# 15_-_PWR_IN_LEDS_BUTTONS_MECH.net
KiCad netlist of a schematic drawn in Altium Designer
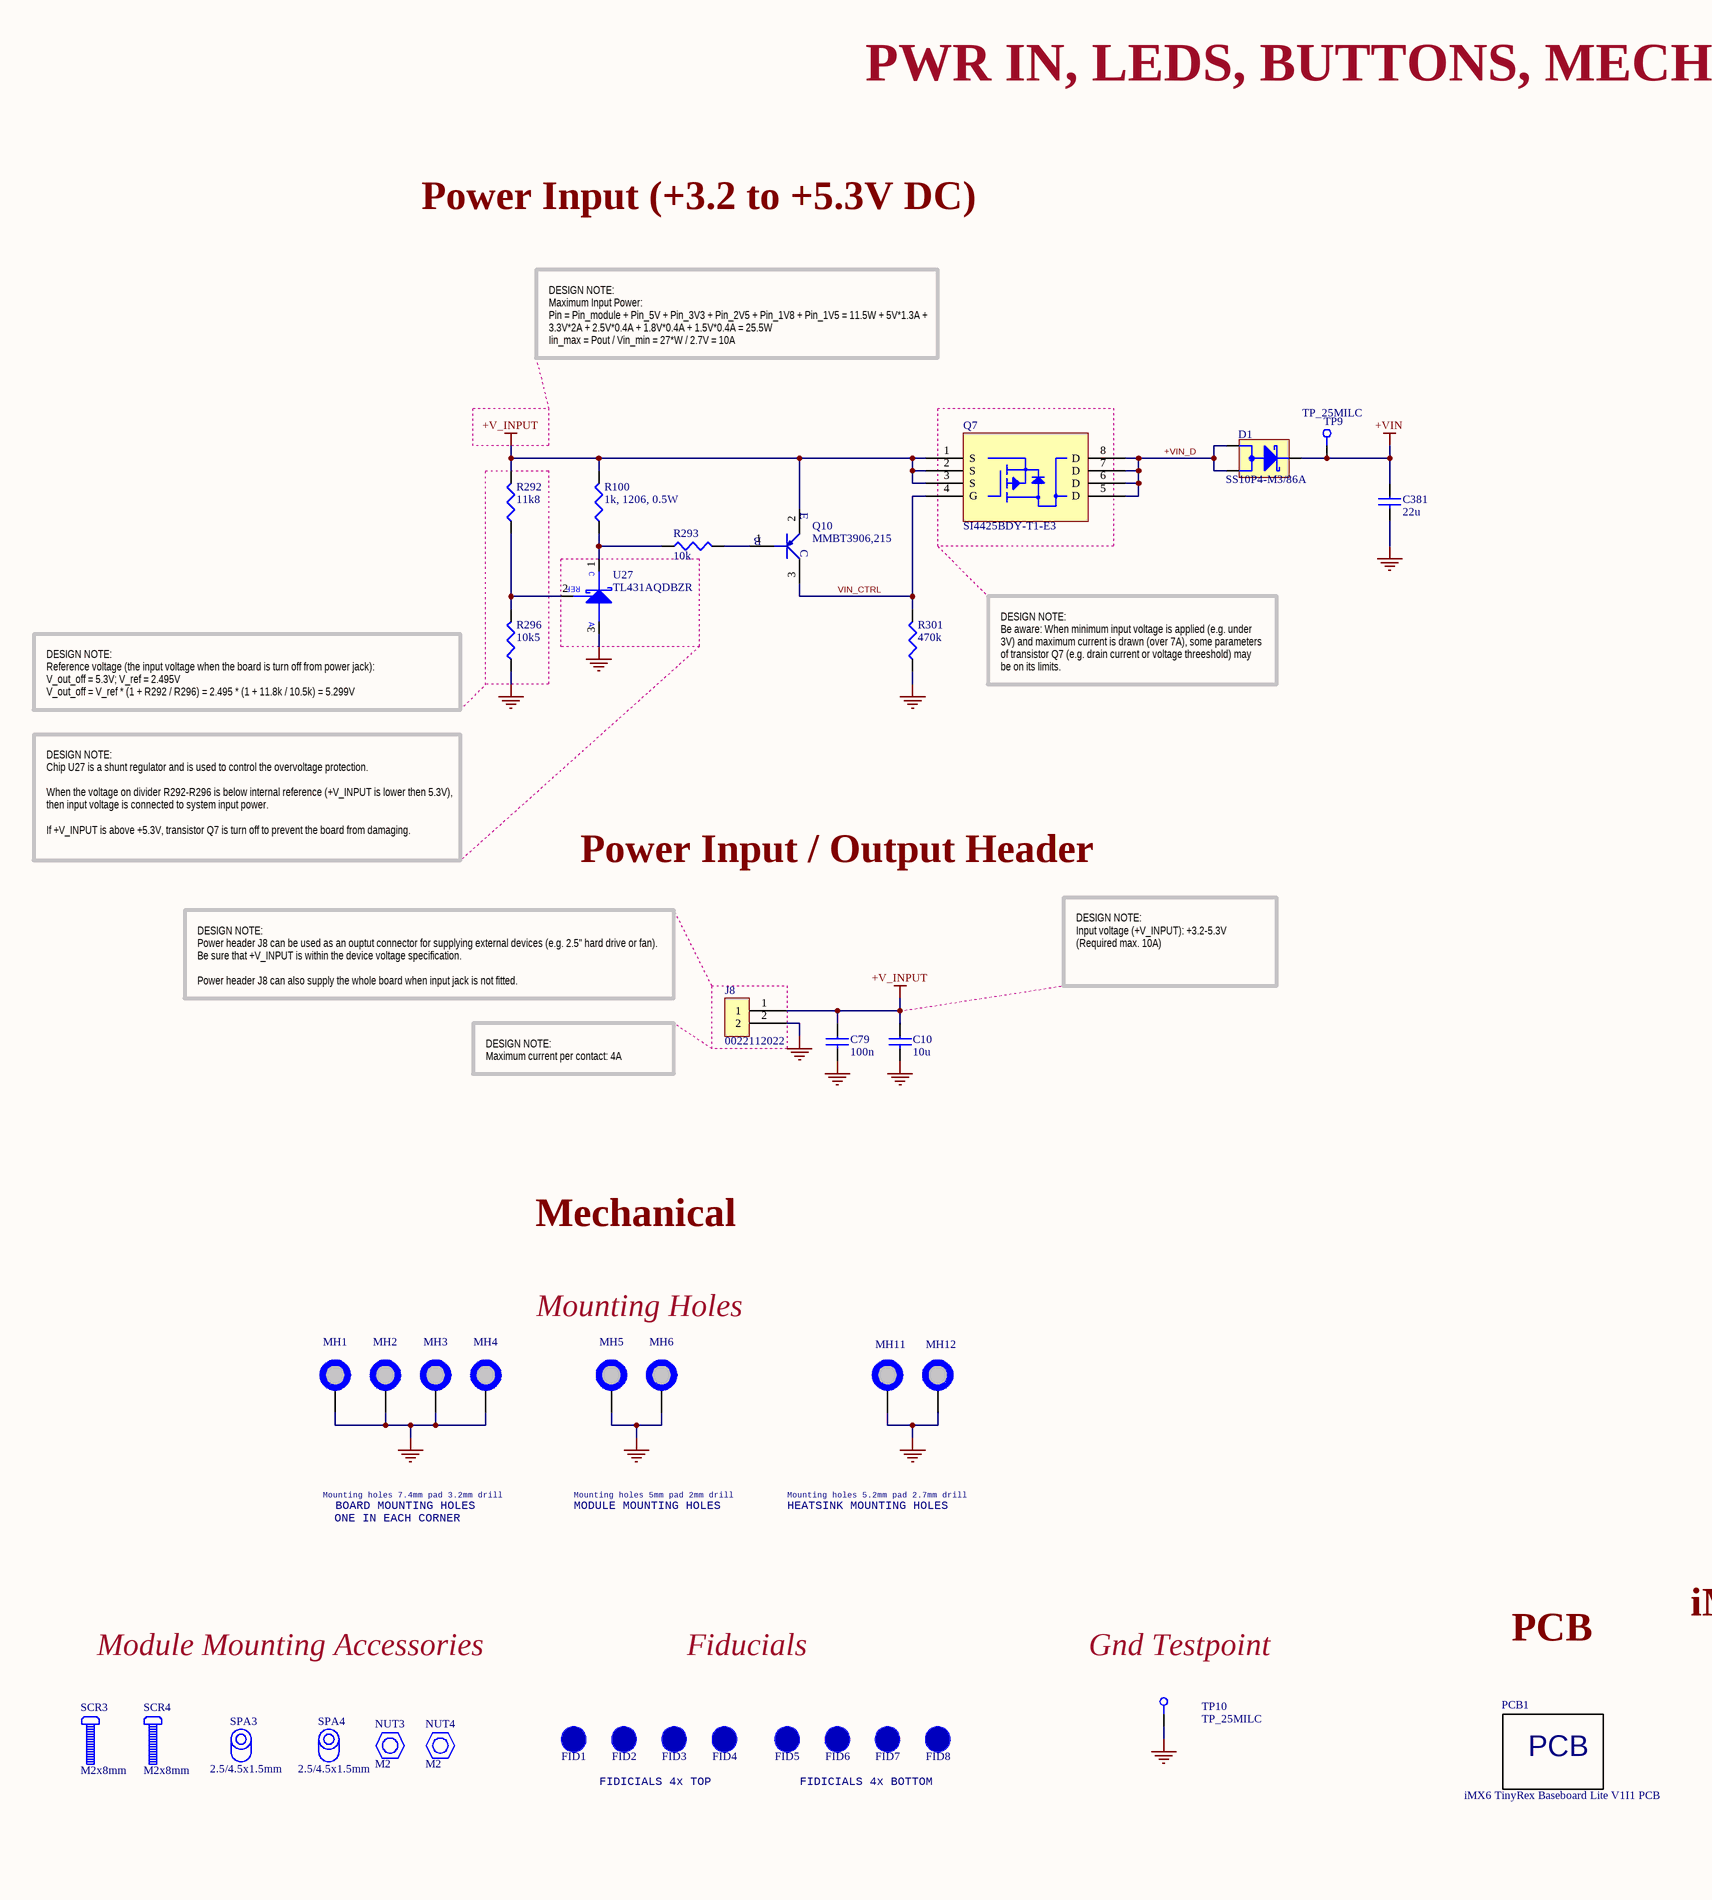
[diagram p0: [15] - PWR IN, LEDS, BUTTONS, MECH.SchDoc, left]
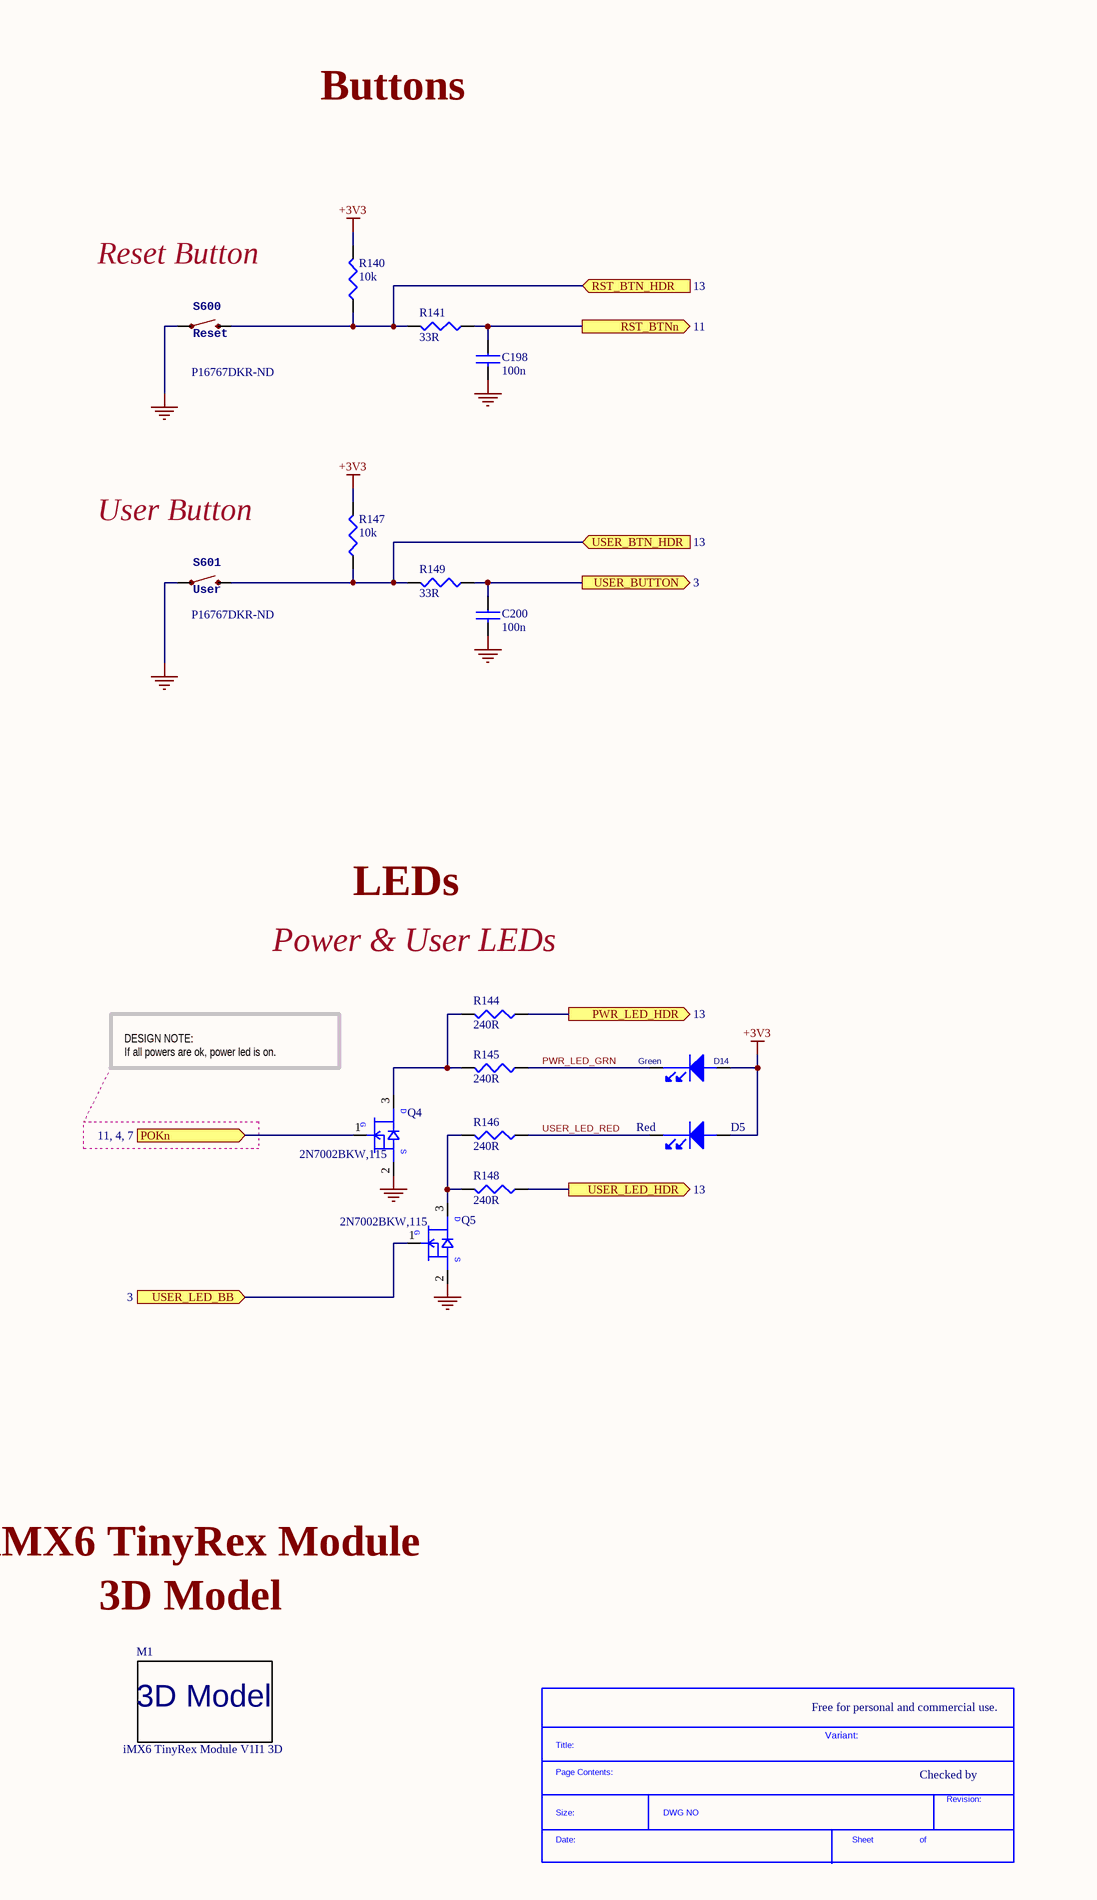
[diagram p1: [15] - PWR IN, LEDS, BUTTONS, MECH.SchDoc, right]

(export (version "E")
  (design (tool "Eeschema 10.0.6"))
  (components
    (comp (ref "C10")
      (value "10u")
      (footprint "C0603")
      (description "CAP CER 10UF 6.3V X5R 20% 0603")
      (fields
        (field (name "MANUFACTURER") "TDK Corporation")
        (field (name "MANUFACTURER PART NUMBER") "C1608X5R0J106M")
      )
      (libsource (lib "Integrated_Library_FEDEVEL_APR_2015") (part "C1608X5R0J106M"))
    )
    (comp (ref "C79")
      (value "100n")
      (footprint "C0402")
      (description "CAP CER .10UF 50V X5R 10% 0402")
      (fields
        (field (name "MANUFACTURER") "TDK Corporation")
        (field (name "MANUFACTURER PART NUMBER") "C1005X5R1H104K")
      )
      (libsource (lib "Integrated_Library_FEDEVEL_APR_2015") (part "C1005X5R1H104K"))
    )
    (comp (ref "C198")
      (value "100n")
      (footprint "C0402")
      (description "CAP CER .10UF 50V X5R 10% 0402")
      (fields
        (field (name "MANUFACTURER") "TDK Corporation")
        (field (name "MANUFACTURER PART NUMBER") "C1005X5R1H104K")
      )
      (libsource (lib "Integrated_Library_FEDEVEL_APR_2015") (part "C1005X5R1H104K"))
    )
    (comp (ref "C200")
      (value "100n")
      (footprint "C0402")
      (description "CAP CER .10UF 50V X5R 10% 0402")
      (fields
        (field (name "MANUFACTURER") "TDK Corporation")
        (field (name "MANUFACTURER PART NUMBER") "C1005X5R1H104K")
      )
      (libsource (lib "Integrated_Library_FEDEVEL_APR_2015") (part "C1005X5R1H104K"))
    )
    (comp (ref "C381")
      (value "22u")
      (footprint "C0603")
      (description "CAP CER 22UF 6.3V 20% X5R 0603")
      (fields
        (field (name "MANUFACTURER") "TDK Corporation")
        (field (name "MANUFACTURER PART NUMBER") "C1608X5R0J226M080AC")
        (field (name ".CREATOR") "MM")
        (field (name ".CHECKED PCB") "MM")
        (field (name ".CHECKED SCH") "MM")
      )
      (libsource (lib "Integrated_Library_FEDEVEL_APR_2015") (part "C1608X5R0J226M080AC"))
    )
    (comp (ref "D1")
      (value "SS10P4-M3/86A")
      (footprint "TO-277A (SMPC)")
      (description "DIODE SCHOTTKY 40V 10A TO277A")
      (fields
        (field (name "MANUFACTURER") "Vishay Semiconductor Diodes Division")
        (field (name ".CHECKED PCB") "MM")
        (field (name ".CHECKED SCH") "MM")
        (field (name ".CREATOR") "MM")
      )
      (libsource (lib "Integrated_Library_FEDEVEL_APR_2015") (part "SS10P4-M3/86A"))
    )
    (comp (ref "D5")
      (value "Red")
      (footprint "LED_0603")
      (description "LED SMARTLED RED 630NM 0603 SMD")
      (fields
        (field (name "MANUFACTURER") "OSRAM Opto Semiconductors Inc")
        (field (name "MANUFACTURER PART NUMBER") "LS L29K-H1J2-1-Z")
      )
      (libsource (lib "Integrated_Library_FEDEVEL_APR_2015") (part "LS L29K-H1J2-1-Z"))
    )
    (comp (ref "D14")
      (value "Green")
      (footprint "LED_0603")
      (description "LED SMARTLED GREEN 570NM 0603")
      (fields
        (field (name "MANUFACTURER") "OSRAM Opto Semiconductors Inc")
        (field (name "MANUFACTURER PART NUMBER") "LG L29K-G2J1-24-Z")
      )
      (libsource (lib "Integrated_Library_FEDEVEL_APR_2015") (part "LG L29K-G2J1-24-Z"))
    )
    (comp (ref "FID1")
      (value "FID_1MMC")
      (footprint "FID_40X120D")
      (description "Fiducial 40mil Diameter, 120mil Mask")
      (libsource (lib "Integrated_Library_FEDEVEL_APR_2015") (part "FID_1MMC"))
    )
    (comp (ref "FID2")
      (value "FID_1MMC")
      (footprint "FID_40X120D")
      (description "Fiducial 40mil Diameter, 120mil Mask")
      (libsource (lib "Integrated_Library_FEDEVEL_APR_2015") (part "FID_1MMC"))
    )
    (comp (ref "FID3")
      (value "FID_1MMC")
      (footprint "FID_40X120D")
      (description "Fiducial 40mil Diameter, 120mil Mask")
      (libsource (lib "Integrated_Library_FEDEVEL_APR_2015") (part "FID_1MMC"))
    )
    (comp (ref "FID4")
      (value "FID_1MMC")
      (footprint "FID_40X120D")
      (description "Fiducial 40mil Diameter, 120mil Mask")
      (libsource (lib "Integrated_Library_FEDEVEL_APR_2015") (part "FID_1MMC"))
    )
    (comp (ref "FID5")
      (value "FID_1MMC")
      (footprint "FID_40X120D")
      (description "Fiducial 40mil Diameter, 120mil Mask")
      (libsource (lib "Integrated_Library_FEDEVEL_APR_2015") (part "FID_1MMC"))
    )
    (comp (ref "FID6")
      (value "FID_1MMC")
      (footprint "FID_40X120D")
      (description "Fiducial 40mil Diameter, 120mil Mask")
      (libsource (lib "Integrated_Library_FEDEVEL_APR_2015") (part "FID_1MMC"))
    )
    (comp (ref "FID7")
      (value "FID_1MMC")
      (footprint "FID_40X120D")
      (description "Fiducial 40mil Diameter, 120mil Mask")
      (libsource (lib "Integrated_Library_FEDEVEL_APR_2015") (part "FID_1MMC"))
    )
    (comp (ref "FID8")
      (value "FID_1MMC")
      (footprint "FID_40X120D")
      (description "Fiducial 40mil Diameter, 120mil Mask")
      (libsource (lib "Integrated_Library_FEDEVEL_APR_2015") (part "FID_1MMC"))
    )
    (comp (ref "J8")
      (value "0022112022")
      (footprint "HDR_1x2_2.54MM_MOLEX_KK")
      (description "CONN HEADER 2POS .100 VERT GOLD")
      (fields
        (field (name "MANUFACTURER") "Molex, LLC")
        (field (name ".CREATOR") "MM")
        (field (name ".CHECKED SCH") "MM")
        (field (name ".CHECKED PCB") "MM, paper model not checked")
      )
      (libsource (lib "Integrated_Library_FEDEVEL_APR_2015") (part "0022112022"))
    )
    (comp (ref "M1")
      (value "iMX6 TinyRex Module V1I1 3D")
      (footprint "iMX6 TinyRex Module 3D")
      (description "3D Model")
      (fields (field (name ".CREATOR") "MM"))
      (libsource (lib "Integrated_Library_FEDEVEL_APR_2015") (part "3D_iMX6_TINYREX_MODULE_V1I1"))
    )
    (comp (ref "MH1")
      (value "MH_7.4MMC_3.2MMD")
      (footprint "MH_7.4MMD_3.2MMD")
      (description "Mounting Hole 7.4mm Diameter, 3.2mm Drill")
      (fields (field (name ".CREATOR") "MM"))
      (libsource (lib "Integrated_Library_FEDEVEL_APR_2015") (part "MH_7.4MMC_3.2MMD"))
    )
    (comp (ref "MH2")
      (value "MH_7.4MMC_3.2MMD")
      (footprint "MH_7.4MMD_3.2MMD")
      (description "Mounting Hole 7.4mm Diameter, 3.2mm Drill")
      (fields (field (name ".CREATOR") "MM"))
      (libsource (lib "Integrated_Library_FEDEVEL_APR_2015") (part "MH_7.4MMC_3.2MMD"))
    )
    (comp (ref "MH3")
      (value "MH_7.4MMC_3.2MMD")
      (footprint "MH_7.4MMD_3.2MMD")
      (description "Mounting Hole 7.4mm Diameter, 3.2mm Drill")
      (fields (field (name ".CREATOR") "MM"))
      (libsource (lib "Integrated_Library_FEDEVEL_APR_2015") (part "MH_7.4MMC_3.2MMD"))
    )
    (comp (ref "MH4")
      (value "MH_7.4MMC_3.2MMD")
      (footprint "MH_7.4MMD_3.2MMD")
      (description "Mounting Hole 7.4mm Diameter, 3.2mm Drill")
      (fields (field (name ".CREATOR") "MM"))
      (libsource (lib "Integrated_Library_FEDEVEL_APR_2015") (part "MH_7.4MMC_3.2MMD"))
    )
    (comp (ref "MH5")
      (value "MH_5MMC_2MMD")
      (footprint "MH_5MMD_2MMD")
      (description "Mounting Hole 5mm Diameter, 2mm Drill")
      (fields (field (name ".CREATOR") "MM"))
      (libsource (lib "Integrated_Library_FEDEVEL_APR_2015") (part "MH_5MMC_2MMD"))
    )
    (comp (ref "MH6")
      (value "MH_5MMC_2MMD")
      (footprint "MH_5MMD_2MMD")
      (description "Mounting Hole 5mm Diameter, 2mm Drill")
      (fields (field (name ".CREATOR") "MM"))
      (libsource (lib "Integrated_Library_FEDEVEL_APR_2015") (part "MH_5MMC_2MMD"))
    )
    (comp (ref "MH11")
      (value "MH_5.2MMC_2.7MMD")
      (footprint "MH_5.2MMD_2.7MMD")
      (description "Mounting Hole 5.2mm Diameter, 2.7mm Drill")
      (fields (field (name ".CREATOR") "MM"))
      (libsource (lib "Integrated_Library_FEDEVEL_APR_2015") (part "MH_5.2MMC_2.7MMD"))
    )
    (comp (ref "MH12")
      (value "MH_5.2MMC_2.7MMD")
      (footprint "MH_5.2MMD_2.7MMD")
      (description "Mounting Hole 5.2mm Diameter, 2.7mm Drill")
      (fields (field (name ".CREATOR") "MM"))
      (libsource (lib "Integrated_Library_FEDEVEL_APR_2015") (part "MH_5.2MMC_2.7MMD"))
    )
    (comp (ref "NUT3")
      (value "M2")
      (footprint "NUT A4 SS M2")
      (description "ROEBUCK - PFP1166 - FULL NUT A4 SS M2 (PK 100)")
      (fields
        (field (name "MANUFACTURER") "ROEBUCK")
        (field (name "MANUFACTURER PART NUMBER") "PFP1166")
        (field (name ".CHECKED SCH") "MM")
      )
      (libsource (lib "Integrated_Library_FEDEVEL_APR_2015") (part "PFP1166"))
    )
    (comp (ref "NUT4")
      (value "M2")
      (footprint "NUT A4 SS M2")
      (description "ROEBUCK - PFP1166 - FULL NUT A4 SS M2 (PK 100)")
      (fields
        (field (name "MANUFACTURER") "ROEBUCK")
        (field (name "MANUFACTURER PART NUMBER") "PFP1166")
        (field (name ".CHECKED SCH") "MM")
      )
      (libsource (lib "Integrated_Library_FEDEVEL_APR_2015") (part "PFP1166"))
    )
    (comp (ref "PCB1")
      (value "iMX6 TinyRex Baseboard Lite V1I1 PCB")
      (fields (field (name ".CREATOR") "MM") (field (name ".CHECKED SCH") "MM"))
      (libsource (lib "Integrated_Library_FEDEVEL_APR_2015") (part "PCB_iMX6_TinyRex_Baseboard_Lite_V1I1"))
    )
    (comp (ref "Q4")
      (value "2N7002BKW,115")
      (footprint "SC70_SOT323")
      (description "MOSFET N-CH 60V 310MA SOT323")
      (fields (field (name "MANUFACTURER") "NXP Semiconductors"))
      (libsource (lib "Integrated_Library_FEDEVEL_APR_2015") (part "2N7002BKW,115"))
    )
    (comp (ref "Q5")
      (value "2N7002BKW,115")
      (footprint "SC70_SOT323")
      (description "MOSFET N-CH 60V 310MA SOT323")
      (fields (field (name "MANUFACTURER") "NXP Semiconductors"))
      (libsource (lib "Integrated_Library_FEDEVEL_APR_2015") (part "2N7002BKW,115"))
    )
    (comp (ref "Q7")
      (value "SI4425BDY-T1-E3")
      (footprint "8_SOIC_3.9MM")
      (description "MOSFET P-CH 30V 8.8A 8-SOIC")
      (fields
        (field (name "MANUFACTURER") "Vishay Siliconix")
        (field (name ".CHECKED PCB") "MM")
        (field (name ".CHECKED SCH") "MM")
        (field (name ".CREATOR") "MM")
      )
      (libsource (lib "Integrated_Library_FEDEVEL_APR_2015") (part "SI4425BDY-T1-E3"))
    )
    (comp (ref "Q10")
      (value "MMBT3906,215")
      (footprint "SOT-23-3-123")
      (description "TRANS PNP 40V 0.2A SOT23")
      (fields
        (field (name "MANUFACTURER") "NXP Semiconductors")
        (field (name ".CHECKED PCB") "MM")
        (field (name ".CHECKED SCH") "MM")
        (field (name ".CREATOR") "MM")
      )
      (libsource (lib "Integrated_Library_FEDEVEL_APR_2015") (part "MMBT3906,215"))
    )
    (comp (ref "R100")
      (value "1k, 1206, 0.5W")
      (footprint "R1206")
      (description "RES SMD 1K OHM 1% 1/2W 1206")
      (fields
        (field (name "MANUFACTURER") "Stackpole Electronics Inc")
        (field (name "MANUFACTURER PART NUMBER") "RNCP1206FTD1K00")
        (field (name ".CHECKED PCB") "MM")
        (field (name ".CHECKED SCH") "MM")
        (field (name ".CREATOR") "MM")
      )
      (libsource (lib "Integrated_Library_FEDEVEL_APR_2015") (part "RNCP1206FTD1K00"))
    )
    (comp (ref "R140")
      (value "10k")
      (footprint "R0402")
      (description "RES 10.0K OHM 1/16W 1% 0402 SMD")
      (fields
        (field (name "MANUFACTURER") "Yageo")
        (field (name "MANUFACTURER PART NUMBER") "RC0402FR-0710KL")
      )
      (libsource (lib "Integrated_Library_FEDEVEL_APR_2015") (part "RC0402FR-0710KL"))
    )
    (comp (ref "R141")
      (value "33R")
      (footprint "R0402")
      (description "RES TF 33 OHM 1% 1/16W 0402")
      (fields
        (field (name "MANUFACTURER") "Stackpole Electronics Inc")
        (field (name "MANUFACTURER PART NUMBER") "RMCF0402FT33R0")
      )
      (libsource (lib "Integrated_Library_FEDEVEL_APR_2015") (part "RMCF0402FT33R0"))
    )
    (comp (ref "R144")
      (value "240R")
      (footprint "R0402")
      (description "RES TF 240 OHM 1% 0.0625W 0402")
      (fields
        (field (name "MANUFACTURER") "Stackpole Electronics Inc")
        (field (name "MANUFACTURER PART NUMBER") "RMCF0402FT240R")
      )
      (libsource (lib "Integrated_Library_FEDEVEL_APR_2015") (part "RMCF0402FT240R"))
    )
    (comp (ref "R145")
      (value "240R")
      (footprint "R0402")
      (description "RES TF 240 OHM 1% 0.0625W 0402")
      (fields
        (field (name "MANUFACTURER") "Stackpole Electronics Inc")
        (field (name "MANUFACTURER PART NUMBER") "RMCF0402FT240R")
      )
      (libsource (lib "Integrated_Library_FEDEVEL_APR_2015") (part "RMCF0402FT240R"))
    )
    (comp (ref "R146")
      (value "240R")
      (footprint "R0402")
      (description "RES TF 240 OHM 1% 0.0625W 0402")
      (fields
        (field (name "MANUFACTURER") "Stackpole Electronics Inc")
        (field (name "MANUFACTURER PART NUMBER") "RMCF0402FT240R")
      )
      (libsource (lib "Integrated_Library_FEDEVEL_APR_2015") (part "RMCF0402FT240R"))
    )
    (comp (ref "R147")
      (value "10k")
      (footprint "R0402")
      (description "RES 10.0K OHM 1/16W 1% 0402 SMD")
      (fields
        (field (name "MANUFACTURER") "Yageo")
        (field (name "MANUFACTURER PART NUMBER") "RC0402FR-0710KL")
      )
      (libsource (lib "Integrated_Library_FEDEVEL_APR_2015") (part "RC0402FR-0710KL"))
    )
    (comp (ref "R148")
      (value "240R")
      (footprint "R0402")
      (description "RES TF 240 OHM 1% 0.0625W 0402")
      (fields
        (field (name "MANUFACTURER") "Stackpole Electronics Inc")
        (field (name "MANUFACTURER PART NUMBER") "RMCF0402FT240R")
      )
      (libsource (lib "Integrated_Library_FEDEVEL_APR_2015") (part "RMCF0402FT240R"))
    )
    (comp (ref "R149")
      (value "33R")
      (footprint "R0402")
      (description "RES TF 33 OHM 1% 1/16W 0402")
      (fields
        (field (name "MANUFACTURER") "Stackpole Electronics Inc")
        (field (name "MANUFACTURER PART NUMBER") "RMCF0402FT33R0")
      )
      (libsource (lib "Integrated_Library_FEDEVEL_APR_2015") (part "RMCF0402FT33R0"))
    )
    (comp (ref "R292")
      (value "11k8")
      (footprint "R0402")
      (description "RES 11.8K OHM 1/16W 1% 0402 SMD")
      (fields
        (field (name "MANUFACTURER") "Vishay Dale")
        (field (name "MANUFACTURER PART NUMBER") "CRCW040211K8FKED")
        (field (name ".CHECKED PCB") "RF")
        (field (name ".CHECKED SCH") "RF")
      )
      (libsource (lib "Integrated_Library_FEDEVEL_APR_2015") (part "CRCW040211K8FKED"))
    )
    (comp (ref "R293")
      (value "10k")
      (footprint "R0402")
      (description "RES 10.0K OHM 1/16W 1% 0402 SMD")
      (fields
        (field (name "MANUFACTURER") "Yageo")
        (field (name "MANUFACTURER PART NUMBER") "RC0402FR-0710KL")
      )
      (libsource (lib "Integrated_Library_FEDEVEL_APR_2015") (part "RC0402FR-0710KL"))
    )
    (comp (ref "R296")
      (value "10k5")
      (footprint "R0402")
      (description "RES 10.5K OHM 1/16W 1% 0402 SMD")
      (fields
        (field (name "MANUFACTURER") "Vishay/Dale")
        (field (name "MANUFACTURER PART NUMBER") "CRCW040210K5FKED")
      )
      (libsource (lib "Integrated_Library_FEDEVEL_APR_2015") (part "CRCW040210K5FKED"))
    )
    (comp (ref "R301")
      (value "470k")
      (footprint "R0402")
      (description "RES 470K OHM 1/16W 1% 0402 SMD")
      (fields
        (field (name "MANUFACTURER") "Vishay Dale")
        (field (name "MANUFACTURER PART NUMBER") "CRCW0402470KFKED")
        (field (name ".CHECKED PCB") "MM")
        (field (name ".CHECKED SCH") "MM")
      )
      (libsource (lib "Integrated_Library_FEDEVEL_APR_2015") (part "CRCW0402470KFKED"))
    )
    (comp (ref "S600")
      (value "Reset")
      (footprint "EVQP7J01K")
      (fields (field (name "SUPPLIER PART NUMBER 1") "P16767DKR-ND"))
      (libsource (lib "PCA_0005_FULL_CB_REV_B") (part "SWITCH-MOMENTARY-2"))
    )
    (comp (ref "S601")
      (value "User")
      (footprint "EVQP7J01K")
      (fields (field (name "SUPPLIER PART NUMBER 1") "P16767DKR-ND"))
      (libsource (lib "pixhawk2") (part "SWITCH-MOMENTARY-2"))
    )
    (comp (ref "SCR3")
      (value "M2x8mm")
      (footprint "SCREW M2x8")
      (description "MACHINE SCREW PAN PHILLIPS M2")
      (fields
        (field (name "MANUFACTURER") "B&F Fastener Supply")
        (field (name "MANUFACTURER PART NUMBER") "MPMS 002 0008 PH")
        (field (name ".CREATOR") "MM")
        (field (name ".CHECKED SCH") "MM")
      )
      (libsource (lib "Integrated_Library_FEDEVEL_APR_2015") (part "MPMS 002 0008 PH"))
    )
    (comp (ref "SCR4")
      (value "M2x8mm")
      (footprint "SCREW M2x8")
      (description "MACHINE SCREW PAN PHILLIPS M2")
      (fields
        (field (name "MANUFACTURER") "B&F Fastener Supply")
        (field (name "MANUFACTURER PART NUMBER") "MPMS 002 0008 PH")
        (field (name ".CREATOR") "MM")
        (field (name ".CHECKED SCH") "MM")
      )
      (libsource (lib "Integrated_Library_FEDEVEL_APR_2015") (part "MPMS 002 0008 PH"))
    )
    (comp (ref "SPA3")
      (value "2.5/4.5x1.5mm")
      (footprint "SPACER 2.5/4.5X1.5MM")
      (description "SPACER 2.5/4.5X1.5MM")
      (fields (field (name ".CREATOR") "MM") (field (name ".CHECKED SCH") "MM"))
      (libsource (lib "Integrated_Library_FEDEVEL_APR_2015") (part "SPACER 2.5/4.5X1.5MM"))
    )
    (comp (ref "SPA4")
      (value "2.5/4.5x1.5mm")
      (footprint "SPACER 2.5/4.5X1.5MM")
      (description "SPACER 2.5/4.5X1.5MM")
      (fields (field (name ".CREATOR") "MM") (field (name ".CHECKED SCH") "MM"))
      (libsource (lib "Integrated_Library_FEDEVEL_APR_2015") (part "SPACER 2.5/4.5X1.5MM"))
    )
    (comp (ref "TP9")
      (value "TP_25MILC")
      (footprint "TP_25C")
      (description "Test Point 25mil")
      (libsource (lib "Integrated_Library_FEDEVEL_APR_2015") (part "TP_25MILC"))
    )
    (comp (ref "TP10")
      (value "TP_25MILC")
      (footprint "TP_25C")
      (description "Test Point 25mil")
      (libsource (lib "Integrated_Library_FEDEVEL_APR_2015") (part "TP_25MILC"))
    )
    (comp (ref "U27")
      (value "TL431AQDBZR")
      (footprint "SOT-23-3-123")
      (description "IC VREF SHUNT ADJ SOT23-3")
      (fields
        (field (name "MANUFACTURER") "Texas Instruments")
        (field (name "TOLERANCE") "±1%")
        (field (name ".CHECKED PCB") "MM")
        (field (name ".CHECKED SCH") "MM")
        (field (name ".CREATOR") "MM")
      )
      (libsource (lib "Integrated_Library_FEDEVEL_APR_2015") (part "TL431AQDBZR"))
    )
  )
  (nets
    (net (code "1") (name "+3V3") (class "Default")
      (node (ref "D14") (pin "2") (pinfunction "ANODE_2") (pintype "passive"))
      (node (ref "D5") (pin "2") (pinfunction "ANODE_2") (pintype "passive"))
      (node (ref "R140") (pin "2") (pinfunction "2_2") (pintype "passive"))
      (node (ref "R147") (pin "2") (pinfunction "2_2") (pintype "passive"))
    )
    (net (code "2") (name "+VIN") (class "Default")
      (node (ref "C381") (pin "1") (pinfunction "1_1") (pintype "passive"))
      (node (ref "D1") (pin "3") (pinfunction "CATHODE_3") (pintype "passive"))
      (node (ref "TP9") (pin "1") (pinfunction "1_1") (pintype "passive"))
    )
    (net (code "3") (name "+V_INPUT") (class "Default")
      (node (ref "C10") (pin "1") (pinfunction "1_1") (pintype "passive"))
      (node (ref "C79") (pin "1") (pinfunction "1_1") (pintype "passive"))
      (node (ref "J8") (pin "1") (pinfunction "1_1") (pintype "passive"))
      (node (ref "Q10") (pin "2") (pinfunction "E_2") (pintype "passive"))
      (node (ref "Q7") (pin "1") (pinfunction "S_1") (pintype "passive"))
      (node (ref "Q7") (pin "2") (pinfunction "S_2") (pintype "passive"))
      (node (ref "Q7") (pin "3") (pinfunction "S_3") (pintype "passive"))
      (node (ref "R100") (pin "2") (pinfunction "2_2") (pintype "passive"))
      (node (ref "R292") (pin "2") (pinfunction "2_2") (pintype "passive"))
    )
    (net (code "4") (name "/+VIN_D") (class "Default")
      (node (ref "D1") (pin "1") (pinfunction "ANODE1_1") (pintype "passive"))
      (node (ref "D1") (pin "2") (pinfunction "ANODE2_2") (pintype "passive"))
      (node (ref "Q7") (pin "5") (pinfunction "D_5") (pintype "passive"))
      (node (ref "Q7") (pin "6") (pinfunction "D_6") (pintype "passive"))
      (node (ref "Q7") (pin "7") (pinfunction "D_7") (pintype "passive"))
      (node (ref "Q7") (pin "8") (pinfunction "D_8") (pintype "passive"))
    )
    (net (code "5") (name "/POKn") (class "Default")
      (node (ref "Q4") (pin "1") (pinfunction "GATE_1") (pintype "passive"))
    )
    (net (code "6") (name "/PWR_LED_GRN") (class "Default")
      (node (ref "D14") (pin "1") (pinfunction "cathode_1") (pintype "passive"))
      (node (ref "R145") (pin "1") (pinfunction "1_1") (pintype "passive"))
    )
    (net (code "7") (name "/PWR_LED_HDR") (class "Default")
      (node (ref "R144") (pin "1") (pinfunction "1_1") (pintype "passive"))
    )
    (net (code "8") (name "/RST_BTN_HDR") (class "Default")
      (node (ref "R140") (pin "1") (pinfunction "1_1") (pintype "passive"))
      (node (ref "R141") (pin "2") (pinfunction "2_2") (pintype "passive"))
      (node (ref "S600") (pin "B3") (pinfunction "2_B3") (pintype "passive"))
    )
    (net (code "9") (name "/RST_BTNn") (class "Default")
      (node (ref "C198") (pin "1") (pinfunction "1_1") (pintype "passive"))
      (node (ref "R141") (pin "1") (pinfunction "1_1") (pintype "passive"))
    )
    (net (code "10") (name "/USER_BTN_HDR") (class "Default")
      (node (ref "R147") (pin "1") (pinfunction "1_1") (pintype "passive"))
      (node (ref "R149") (pin "2") (pinfunction "2_2") (pintype "passive"))
      (node (ref "S601") (pin "B3") (pinfunction "2_B3") (pintype "passive"))
    )
    (net (code "11") (name "/USER_BUTTON") (class "Default")
      (node (ref "C200") (pin "1") (pinfunction "1_1") (pintype "passive"))
      (node (ref "R149") (pin "1") (pinfunction "1_1") (pintype "passive"))
    )
    (net (code "12") (name "/USER_LED_BB") (class "Default")
      (node (ref "Q5") (pin "1") (pinfunction "GATE_1") (pintype "passive"))
    )
    (net (code "13") (name "/USER_LED_HDR") (class "Default")
      (node (ref "R148") (pin "1") (pinfunction "1_1") (pintype "passive"))
    )
    (net (code "14") (name "/USER_LED_RED") (class "Default")
      (node (ref "D5") (pin "1") (pinfunction "cathode_1") (pintype "passive"))
      (node (ref "R146") (pin "1") (pinfunction "1_1") (pintype "passive"))
    )
    (net (code "15") (name "/VIN_CTRL") (class "Default")
      (node (ref "Q10") (pin "3") (pinfunction "C_3") (pintype "passive"))
      (node (ref "Q7") (pin "4") (pinfunction "G_4") (pintype "passive"))
      (node (ref "R301") (pin "2") (pinfunction "2_2") (pintype "passive"))
    )
    (net (code "16") (name "GND") (class "Default")
      (node (ref "C10") (pin "2") (pinfunction "2_2") (pintype "passive"))
      (node (ref "C198") (pin "2") (pinfunction "2_2") (pintype "passive"))
      (node (ref "C200") (pin "2") (pinfunction "2_2") (pintype "passive"))
      (node (ref "C381") (pin "2") (pinfunction "2_2") (pintype "passive"))
      (node (ref "C79") (pin "2") (pinfunction "2_2") (pintype "passive"))
      (node (ref "J8") (pin "2") (pinfunction "2_2") (pintype "passive"))
      (node (ref "MH1") (pin "1") (pinfunction "1_1") (pintype "passive"))
      (node (ref "MH11") (pin "1") (pinfunction "1_1") (pintype "passive"))
      (node (ref "MH12") (pin "1") (pinfunction "1_1") (pintype "passive"))
      (node (ref "MH2") (pin "1") (pinfunction "1_1") (pintype "passive"))
      (node (ref "MH3") (pin "1") (pinfunction "1_1") (pintype "passive"))
      (node (ref "MH4") (pin "1") (pinfunction "1_1") (pintype "passive"))
      (node (ref "MH5") (pin "1") (pinfunction "1_1") (pintype "passive"))
      (node (ref "MH6") (pin "1") (pinfunction "1_1") (pintype "passive"))
      (node (ref "Q4") (pin "2") (pinfunction "SOURCE_2") (pintype "passive"))
      (node (ref "Q5") (pin "2") (pinfunction "SOURCE_2") (pintype "passive"))
      (node (ref "R296") (pin "1") (pinfunction "1_1") (pintype "passive"))
      (node (ref "R301") (pin "1") (pinfunction "1_1") (pintype "passive"))
      (node (ref "S600") (pin "A1") (pinfunction "1_A1") (pintype "passive"))
      (node (ref "S601") (pin "A1") (pinfunction "1_A1") (pintype "passive"))
      (node (ref "TP10") (pin "1") (pinfunction "1_1") (pintype "passive"))
      (node (ref "U27") (pin "3") (pinfunction "ANODE_3") (pintype "passive"))
    )
    (net (code "17") (name "Net-(Q4-DRAIN)") (class "Default")
      (node (ref "Q4") (pin "3") (pinfunction "DRAIN_3") (pintype "passive"))
      (node (ref "R144") (pin "2") (pinfunction "2_2") (pintype "passive"))
      (node (ref "R145") (pin "2") (pinfunction "2_2") (pintype "passive"))
    )
    (net (code "18") (name "Net-(Q5-DRAIN)") (class "Default")
      (node (ref "Q5") (pin "3") (pinfunction "DRAIN_3") (pintype "passive"))
      (node (ref "R146") (pin "2") (pinfunction "2_2") (pintype "passive"))
      (node (ref "R148") (pin "2") (pinfunction "2_2") (pintype "passive"))
    )
    (net (code "19") (name "Net-(Q10-B)") (class "Default")
      (node (ref "Q10") (pin "1") (pinfunction "B_1") (pintype "passive"))
      (node (ref "R293") (pin "2") (pinfunction "2_2") (pintype "passive"))
    )
    (net (code "20") (name "Net-(U27-REF)") (class "Default")
      (node (ref "R292") (pin "1") (pinfunction "1_1") (pintype "passive"))
      (node (ref "R296") (pin "2") (pinfunction "2_2") (pintype "passive"))
      (node (ref "U27") (pin "2") (pinfunction "REF_2") (pintype "passive"))
    )
    (net (code "21") (name "Net-(U27-cathode)") (class "Default")
      (node (ref "R100") (pin "1") (pinfunction "1_1") (pintype "passive"))
      (node (ref "R293") (pin "1") (pinfunction "1_1") (pintype "passive"))
      (node (ref "U27") (pin "1") (pinfunction "cathode_1") (pintype "passive"))
    )
  )
)
